# encoder.net
KiCad netlist of a schematic drawn in EasyEDA Pro
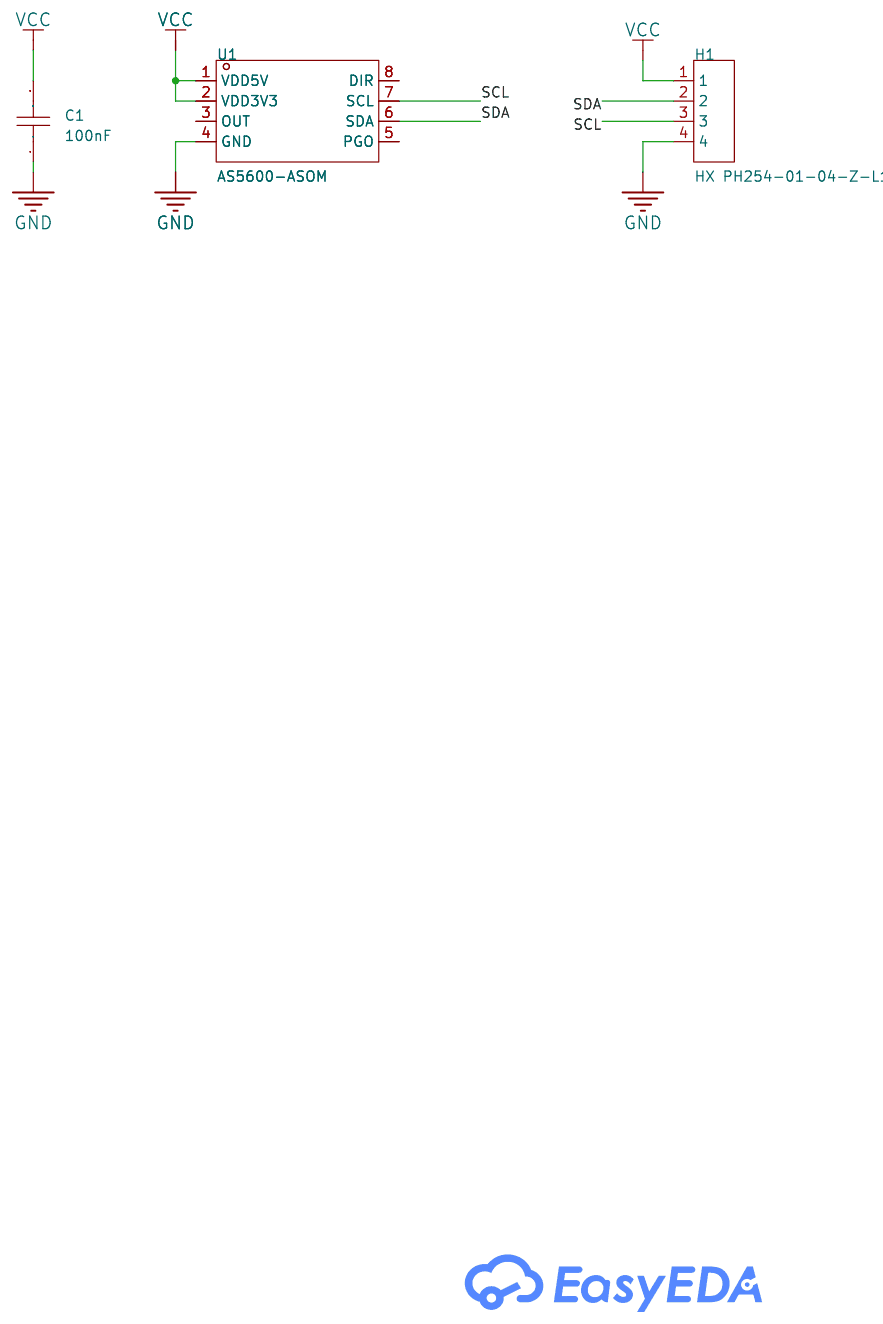
[diagram p0: schematic sheet]

(export (version "E")
  (design (tool "Eeschema 10.0.6"))
  (components
    (comp (ref "C1")
      (value "100nF")
      (footprint "easyedapro:C0805")
      (description "Capacitance:100nF Tolerance:±10% Tolerance:±10% Voltage Rating:50V Temperature Coefficient:X7R")
      (fields
        (field (name "Manufacturer Part") "CC0805KRX7R9BB104")
        (field (name "Manufacturer") "YAGEO(国巨)")
      )
      (libsource (lib "easyedapro") (part "CC0805KRX7R9BB104"))
    )
    (comp (ref "H1")
      (value "HX PH254-01-04-Z-L11.5 straight pin header")
      (footprint "easyedapro:HDR-TH_4P-HX-PH254-01-04-Z-L11.5")
      (fields (field (name "Manufacturer") "hanxia(韩下)"))
      (libsource (lib "easyedapro") (part "HX PH254-01-04-Z-L11.5 STRAIGHT PIN HEADER"))
    )
    (comp (ref "U1")
      (value "AS5600-ASOM")
      (footprint "easyedapro:SOIC-8_L5.0-W4.0-P1.27-LS6.0-BL")
      (description "Supply Voltage:5V；3.3V Supply Voltage:5V；3.3V Rotation Angle:0°~360° Rotation Angle:0°~360°")
      (fields (field (name "Manufacturer") "ams(艾迈斯半导体)"))
      (libsource (lib "easyedapro") (part "AS5600-ASOM"))
    )
  )
  (nets
    (net (code "1") (name "/SCL") (class "Default")
      (node (ref "H1") (pin "3") (pinfunction "3_3") (pintype "unspecified"))
      (node (ref "U1") (pin "7") (pinfunction "SCL_7") (pintype "unspecified"))
    )
    (net (code "2") (name "/SDA") (class "Default")
      (node (ref "H1") (pin "2") (pinfunction "2_2") (pintype "unspecified"))
      (node (ref "U1") (pin "6") (pinfunction "SDA_6") (pintype "unspecified"))
    )
    (net (code "3") (name "GND") (class "Default")
      (node (ref "C1") (pin "1") (pinfunction "1_1") (pintype "unspecified"))
      (node (ref "H1") (pin "4") (pinfunction "4_4") (pintype "unspecified"))
      (node (ref "U1") (pin "4") (pinfunction "GND_4") (pintype "unspecified"))
    )
    (net (code "4") (name "VCC") (class "Default")
      (node (ref "C1") (pin "2") (pinfunction "2_2") (pintype "unspecified"))
      (node (ref "H1") (pin "1") (pinfunction "1_1") (pintype "unspecified"))
      (node (ref "U1") (pin "1") (pinfunction "VDD5V_1") (pintype "unspecified"))
      (node (ref "U1") (pin "2") (pinfunction "VDD3V3_2") (pintype "unspecified"))
    )
    (net (code "5") (name "unconnected-(U1-DIR-Pad8)") (class "Default")
      (node (ref "U1") (pin "8") (pinfunction "DIR_8") (pintype "unspecified"))
    )
    (net (code "6") (name "unconnected-(U1-OUT-Pad3)") (class "Default")
      (node (ref "U1") (pin "3") (pinfunction "OUT_3") (pintype "unspecified"))
    )
    (net (code "7") (name "unconnected-(U1-PGO-Pad5)") (class "Default")
      (node (ref "U1") (pin "5") (pinfunction "PGO_5") (pintype "unspecified"))
    )
  )
)
